# MCU.net
KiCad netlist of a schematic drawn in Altium Designer
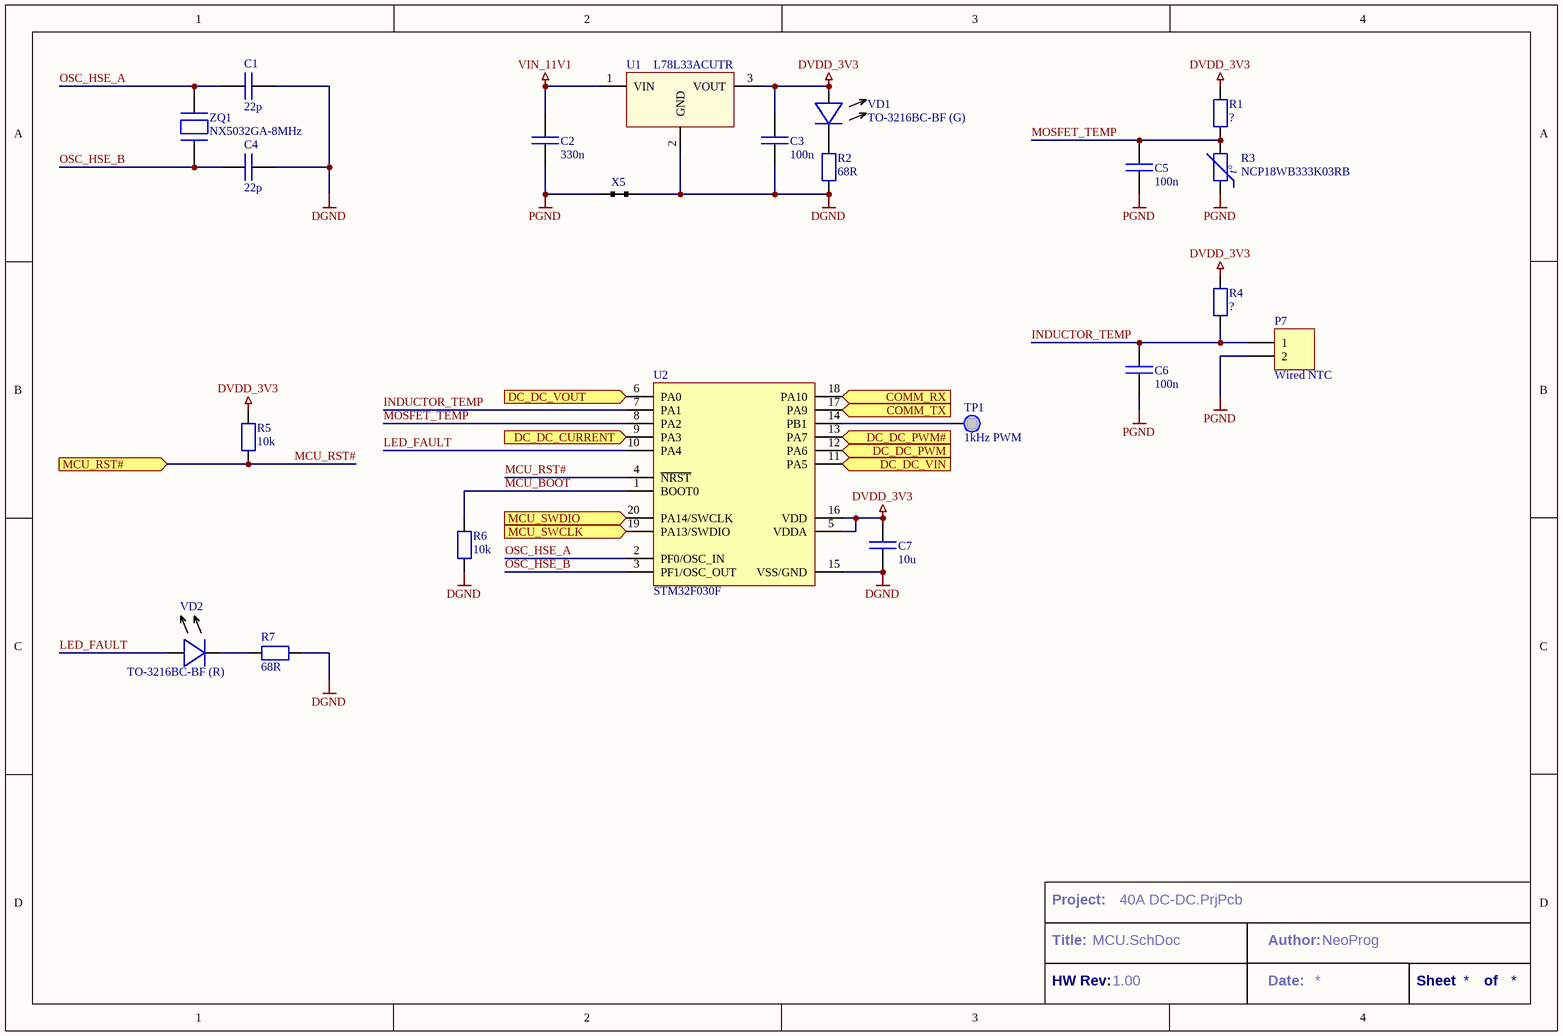
[diagram p0: MCU.SchDoc]

(export (version "E")
  (design (tool "Eeschema 10.0.6"))
  (components
    (comp (ref "C1")
      (value "22p")
      (footprint "C_0603/1608")
      (description "Non-polarized capacitor")
      (libsource (lib "passive") (part "Capacitor"))
    )
    (comp (ref "C2")
      (value "330n")
      (footprint "C_0805/2012")
      (description "Non-polarized capacitor")
      (libsource (lib "passive") (part "Capacitor"))
    )
    (comp (ref "C3")
      (value "100n")
      (footprint "C_0805/2012")
      (description "Non-polarized capacitor")
      (libsource (lib "passive") (part "Capacitor"))
    )
    (comp (ref "C4")
      (value "22p")
      (footprint "C_0603/1608")
      (description "Non-polarized capacitor")
      (libsource (lib "passive") (part "Capacitor"))
    )
    (comp (ref "C5")
      (value "100n")
      (footprint "C_0603/1608")
      (description "Non-polarized capacitor")
      (libsource (lib "passive") (part "Capacitor"))
    )
    (comp (ref "C6")
      (value "100n")
      (footprint "C_0603/1608")
      (description "Non-polarized capacitor")
      (libsource (lib "passive") (part "Capacitor"))
    )
    (comp (ref "C7")
      (value "10u")
      (footprint "C_0603/1608")
      (description "Non-polarized capacitor")
      (libsource (lib "passive") (part "Capacitor"))
    )
    (comp (ref "P7")
      (value "Wired NTC")
      (footprint "HDR_SMD_1X2_1.50")
      (description "Header, 2-Pin")
      (fields (field (name "PUBLISHER") "Altium Limited"))
      (libsource (lib "connectors") (part "Header 2"))
    )
    (comp (ref "R1")
      (value "?")
      (footprint "R_0603/1608")
      (description "Resistor")
      (libsource (lib "passive") (part "Resistor"))
    )
    (comp (ref "R2")
      (value "68R")
      (footprint "R_0603/1608")
      (description "Resistor")
      (libsource (lib "passive") (part "Resistor"))
    )
    (comp (ref "R3")
      (value "NCP18WB333K03RB")
      (footprint "R_0603/1608")
      (description "Termistor")
      (libsource (lib "passive") (part "Termistor"))
    )
    (comp (ref "R4")
      (value "?")
      (footprint "R_0603/1608")
      (description "Resistor")
      (libsource (lib "passive") (part "Resistor"))
    )
    (comp (ref "R5")
      (value "10k")
      (footprint "R_0603/1608")
      (description "Resistor")
      (libsource (lib "passive") (part "Resistor"))
    )
    (comp (ref "R6")
      (value "10k")
      (footprint "R_0603/1608")
      (description "Resistor")
      (libsource (lib "passive") (part "Resistor"))
    )
    (comp (ref "R7")
      (value "68R")
      (footprint "R_0603/1608")
      (description "Resistor")
      (libsource (lib "passive") (part "Resistor"))
    )
    (comp (ref "TP1")
      (value "1kHz PWM")
      (footprint "TP_SMD_D1.00")
      (description "Test point")
      (libsource (lib "connectors") (part "Test point"))
    )
    (comp (ref "U1")
      (value "L78L33ACUTR")
      (footprint "SOT89")
      (description "LDO voltage regulator")
      (libsource (lib "power") (part "L78L"))
    )
    (comp (ref "U2")
      (value "STM32F030F")
      (footprint "TSSOP20")
      (description "32-bit Cortex-M0")
      (libsource (lib "MCU and memory") (part "STM32F030F"))
    )
    (comp (ref "VD1")
      (value "TO-3216BC-BF (G)")
      (footprint "LED_0603/1608")
      (description "LED")
      (libsource (lib "indication") (part "LED"))
    )
    (comp (ref "VD2")
      (value "TO-3216BC-BF (R)")
      (footprint "LED_0603/1608")
      (description "LED")
      (libsource (lib "") (part "LED_1"))
    )
    (comp (ref "X5")
      (value "~")
      (footprint "NET_TIE_0.8")
      (description "Net tie")
      (libsource (lib "connectors") (part "Net tie"))
    )
    (comp (ref "ZQ1")
      (value "NX5032GA-8MHz")
      (footprint "OSC_2PINS SMD")
      (description "Crystal oscillator")
      (libsource (lib "passive") (part "Crystal oscillator"))
    )
  )
  (nets
    (net (code "1") (name "/COMM_RX") (class "Default")
      (node (ref "U2") (pin "18") (pinfunction "PA10_18") (pintype "passive"))
    )
    (net (code "2") (name "/COMM_TX") (class "Default")
      (node (ref "U2") (pin "17") (pinfunction "PA9_17") (pintype "passive"))
    )
    (net (code "3") (name "/DC_DC_CURRENT") (class "Default")
      (node (ref "U2") (pin "9") (pinfunction "PA3_9") (pintype "passive"))
    )
    (net (code "4") (name "/DC_DC_PWM") (class "Default")
      (node (ref "U2") (pin "12") (pinfunction "PA6_12") (pintype "passive"))
    )
    (net (code "5") (name "/DC_DC_PWM#") (class "Default")
      (node (ref "U2") (pin "13") (pinfunction "PA7_13") (pintype "passive"))
    )
    (net (code "6") (name "/DC_DC_VIN") (class "Default")
      (node (ref "U2") (pin "11") (pinfunction "PA5_11") (pintype "passive"))
    )
    (net (code "7") (name "/DC_DC_VOUT") (class "Default")
      (node (ref "U2") (pin "6") (pinfunction "PA0_6") (pintype "passive"))
    )
    (net (code "8") (name "/INDUCTOR_TEMP") (class "Default")
      (node (ref "C6") (pin "1") (pintype "passive"))
      (node (ref "P7") (pin "1") (pinfunction "1_1") (pintype "passive"))
      (node (ref "R4") (pin "1") (pintype "passive"))
      (node (ref "U2") (pin "7") (pinfunction "PA1_7") (pintype "passive"))
    )
    (net (code "9") (name "/LED_FAULT") (class "Default")
      (node (ref "U2") (pin "10") (pinfunction "PA4_10") (pintype "passive"))
      (node (ref "VD2") (pin "A") (pinfunction "Anode_A") (pintype "passive"))
    )
    (net (code "10") (name "/MCU_BOOT") (class "Default")
      (node (ref "R6") (pin "2") (pintype "passive"))
      (node (ref "U2") (pin "1") (pinfunction "BOOT0_1") (pintype "passive"))
    )
    (net (code "11") (name "/MCU_RST#") (class "Default")
      (node (ref "R5") (pin "1") (pintype "passive"))
      (node (ref "U2") (pin "4") (pinfunction "~{NRST}_4") (pintype "passive"))
    )
    (net (code "12") (name "/MCU_SWCLK") (class "Default")
      (node (ref "U2") (pin "19") (pinfunction "PA13/SWDIO_19") (pintype "passive"))
    )
    (net (code "13") (name "/MCU_SWDIO") (class "Default")
      (node (ref "U2") (pin "20") (pinfunction "PA14/SWCLK_20") (pintype "passive"))
    )
    (net (code "14") (name "/MOSFET_TEMP") (class "Default")
      (node (ref "C5") (pin "1") (pintype "passive"))
      (node (ref "R1") (pin "1") (pintype "passive"))
      (node (ref "R3") (pin "2") (pintype "passive"))
      (node (ref "U2") (pin "8") (pinfunction "PA2_8") (pintype "passive"))
    )
    (net (code "15") (name "/OSC_HSE_A") (class "Default")
      (node (ref "C1") (pin "1") (pintype "passive"))
      (node (ref "U2") (pin "2") (pinfunction "PF0/OSC_IN_2") (pintype "passive"))
      (node (ref "ZQ1") (pin "2") (pintype "passive"))
    )
    (net (code "16") (name "/OSC_HSE_B") (class "Default")
      (node (ref "C4") (pin "1") (pintype "passive"))
      (node (ref "U2") (pin "3") (pinfunction "PF1/OSC_OUT_3") (pintype "passive"))
      (node (ref "ZQ1") (pin "1") (pintype "passive"))
    )
    (net (code "17") (name "DGND") (class "Default")
      (node (ref "C1") (pin "2") (pintype "passive"))
      (node (ref "C3") (pin "2") (pintype "passive"))
      (node (ref "C4") (pin "2") (pintype "passive"))
      (node (ref "C7") (pin "2") (pintype "passive"))
      (node (ref "R2") (pin "1") (pintype "passive"))
      (node (ref "R6") (pin "1") (pintype "passive"))
      (node (ref "R7") (pin "2") (pintype "passive"))
      (node (ref "U1") (pin "2") (pinfunction "GND_2") (pintype "power_in"))
      (node (ref "U2") (pin "15") (pinfunction "VSS/GND_15") (pintype "passive"))
      (node (ref "X5") (pin "2") (pintype "passive"))
    )
    (net (code "18") (name "DVDD_3V3") (class "Default")
      (node (ref "C3") (pin "1") (pintype "passive"))
      (node (ref "C7") (pin "1") (pintype "passive"))
      (node (ref "R1") (pin "2") (pintype "passive"))
      (node (ref "R4") (pin "2") (pintype "passive"))
      (node (ref "R5") (pin "2") (pintype "passive"))
      (node (ref "U1") (pin "3") (pinfunction "VOUT_3") (pintype "power_in"))
      (node (ref "U2") (pin "16") (pinfunction "VDD_16") (pintype "passive"))
      (node (ref "U2") (pin "5") (pinfunction "VDDA_5") (pintype "passive"))
      (node (ref "VD1") (pin "A") (pinfunction "Anode_A") (pintype "passive"))
    )
    (net (code "19") (name "Net-(U2-PB1)") (class "Default")
      (node (ref "TP1") (pin "1") (pintype "passive"))
      (node (ref "U2") (pin "14") (pinfunction "PB1_14") (pintype "passive"))
    )
    (net (code "20") (name "Net-(VD1-Cathode)") (class "Default")
      (node (ref "R2") (pin "2") (pintype "passive"))
      (node (ref "VD1") (pin "C") (pinfunction "Cathode_C") (pintype "passive"))
    )
    (net (code "21") (name "Net-(VD2-Cathode)") (class "Default")
      (node (ref "R7") (pin "1") (pintype "passive"))
      (node (ref "VD2") (pin "C") (pinfunction "Cathode_C") (pintype "passive"))
    )
    (net (code "22") (name "PGND") (class "Default")
      (node (ref "C2") (pin "2") (pintype "passive"))
      (node (ref "C5") (pin "2") (pintype "passive"))
      (node (ref "C6") (pin "2") (pintype "passive"))
      (node (ref "P7") (pin "2") (pinfunction "2_2") (pintype "passive"))
      (node (ref "R3") (pin "1") (pintype "passive"))
      (node (ref "X5") (pin "1") (pintype "passive"))
    )
    (net (code "23") (name "VIN_11V1") (class "Default")
      (node (ref "C2") (pin "1") (pintype "passive"))
      (node (ref "U1") (pin "1") (pinfunction "VIN_1") (pintype "power_in"))
    )
    (net (code "24") (name "unconnected-(U2-EP-Pad0)") (class "Default")
      (node (ref "U2") (pin "0") (pinfunction "EP_0") (pintype "passive"))
    )
  )
)
